# kr3_imp_3_2.net
KiCad netlist of a schematic drawn in Altium Designer
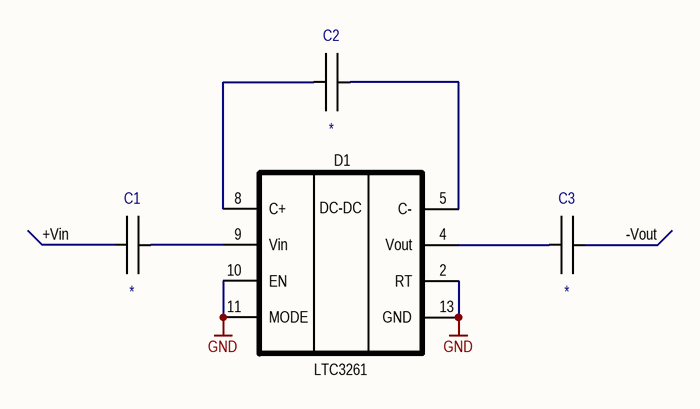
[diagram p0: kr3_imp_3_2.SchDoc]

(export (version "E")
  (design (tool "Eeschema 10.0.6"))
  (components
    (comp (ref "C1")
      (value "*Ф ±* * * *, *")
      (fields (field (name "ALTIUM_VALUE") "*"))
      (libsource (lib "STO") (part "C"))
    )
    (comp (ref "C2")
      (value "*Ф ±* * * *, *")
      (fields (field (name "ALTIUM_VALUE") "*"))
      (libsource (lib "STO") (part "C"))
    )
    (comp (ref "C3")
      (value "*Ф ±* * * *, *")
      (fields (field (name "ALTIUM_VALUE") "*"))
      (libsource (lib "STO") (part "C"))
    )
    (comp (ref "D1") (value "LTC3261") (libsource (lib "STO") (part "LTC3261")))
  )
  (nets
    (net (code "1") (name "/+Vin") (class "Default")
      (node (ref "C1") (pin "2") (pinfunction "2_2") (pintype "passive"))
    )
    (net (code "2") (name "/-Vout") (class "Default")
      (node (ref "C3") (pin "1") (pinfunction "1_1") (pintype "passive"))
    )
    (net (code "3") (name "GND") (class "Default")
      (node (ref "D1") (pin "10") (pinfunction "EN_10") (pintype "passive"))
      (node (ref "D1") (pin "11") (pinfunction "MODE_11") (pintype "passive"))
      (node (ref "D1") (pin "13") (pinfunction "GND_13") (pintype "passive"))
      (node (ref "D1") (pin "2") (pinfunction "RT_2") (pintype "passive"))
    )
    (net (code "4") (name "Net-(D1-C+)") (class "Default")
      (node (ref "C2") (pin "2") (pinfunction "2_2") (pintype "passive"))
      (node (ref "D1") (pin "8") (pinfunction "C+_8") (pintype "passive"))
    )
    (net (code "5") (name "Net-(D1-C-)") (class "Default")
      (node (ref "C2") (pin "1") (pinfunction "1_1") (pintype "passive"))
      (node (ref "D1") (pin "5") (pinfunction "C-_5") (pintype "passive"))
    )
    (net (code "6") (name "Net-(D1-Vin)") (class "Default")
      (node (ref "C1") (pin "1") (pinfunction "1_1") (pintype "passive"))
      (node (ref "D1") (pin "9") (pinfunction "Vin_9") (pintype "passive"))
    )
    (net (code "7") (name "Net-(D1-Vout)") (class "Default")
      (node (ref "C3") (pin "2") (pinfunction "2_2") (pintype "passive"))
      (node (ref "D1") (pin "4") (pinfunction "Vout_4") (pintype "passive"))
    )
  )
)
